# Sheet1.net
KiCad netlist of a schematic drawn in Altium Designer
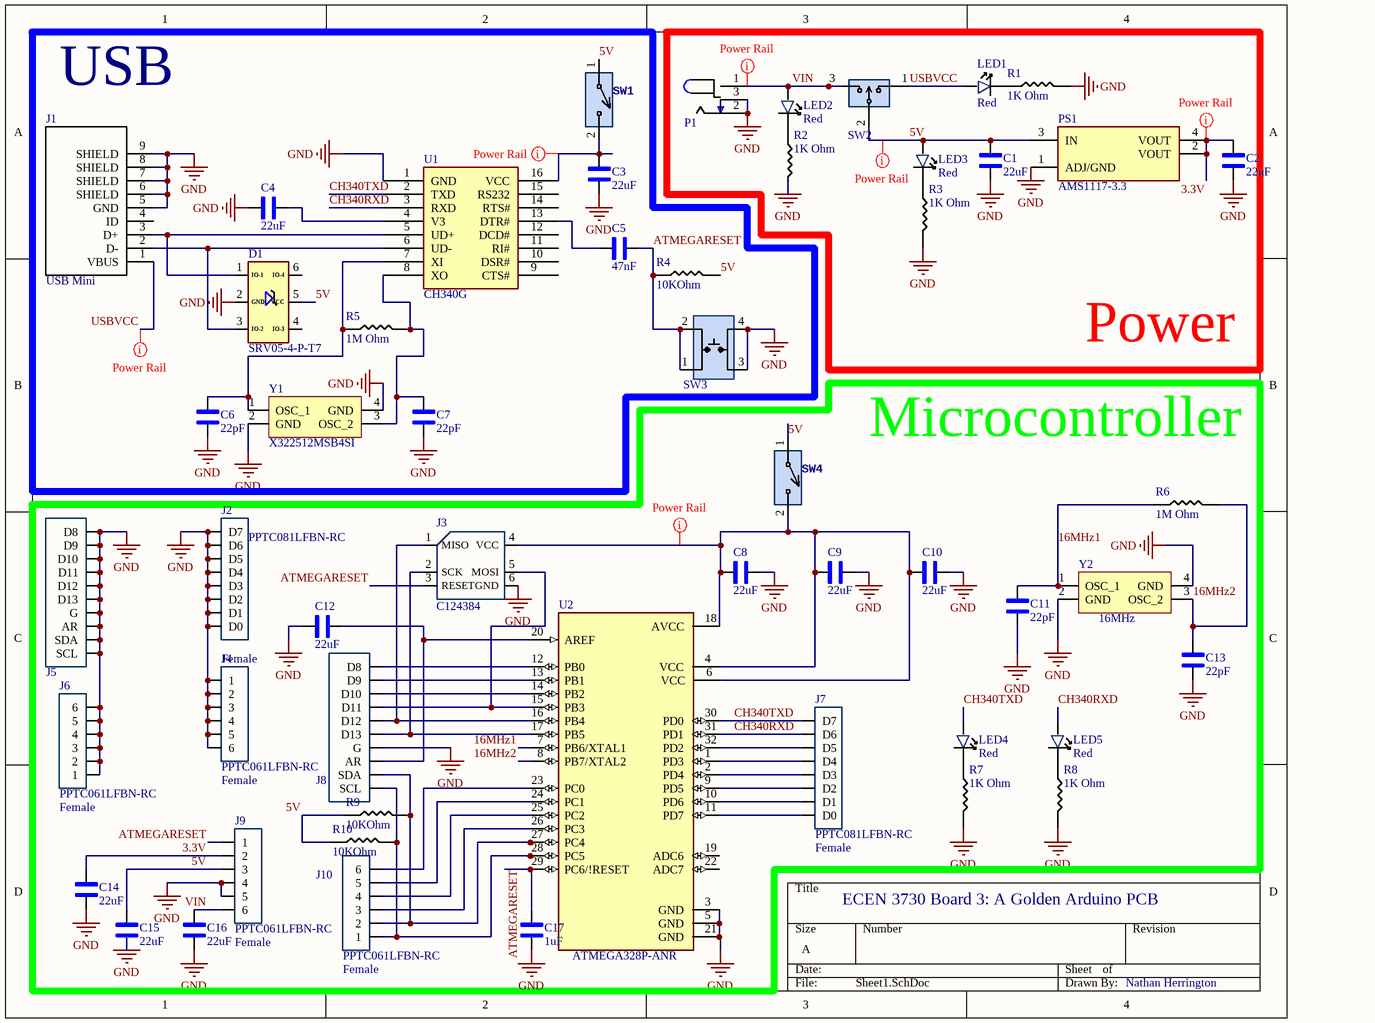
[diagram p0: Sheet1.SchDoc]

(export (version "E")
  (design (tool "Eeschema 10.0.6"))
  (components
    (comp (ref "C1")
      (value "22uF")
      (footprint "1206_Passive_Capacitor")
      (description "22uF ±10% 25V X5R 1206 Multilayer Ceramic Capacitors MLCC - SMD/SMT RoHS")
      (fields (field (name "MFR PART #") "CL31A226KAHNNNE") (field (name "LCSC PART#") "C12891"))
      (libsource (lib "ECEN5730Lib_2023_05_DS") (part "C_22uF_1206"))
    )
    (comp (ref "C2")
      (value "22uF")
      (footprint "1206_Passive_Capacitor")
      (description "22uF ±10% 25V X5R 1206 Multilayer Ceramic Capacitors MLCC - SMD/SMT RoHS")
      (fields (field (name "MFR PART #") "CL31A226KAHNNNE") (field (name "LCSC PART#") "C12891"))
      (libsource (lib "ECEN5730Lib_2023_05_DS") (part "C_22uF_1206"))
    )
    (comp (ref "C3")
      (value "22uF")
      (footprint "1206_Passive_Capacitor")
      (description "22uF ±10% 25V X5R 1206 Multilayer Ceramic Capacitors MLCC - SMD/SMT RoHS")
      (fields (field (name "MFR PART #") "CL31A226KAHNNNE") (field (name "LCSC PART#") "C12891"))
      (libsource (lib "ECEN5730Lib_2023_05_DS") (part "C_22uF_1206"))
    )
    (comp (ref "C4")
      (value "22uF")
      (footprint "1206_Passive_Capacitor")
      (description "22uF ±10% 25V X5R 1206 Multilayer Ceramic Capacitors MLCC - SMD/SMT RoHS")
      (fields (field (name "MFR PART #") "CL31A226KAHNNNE") (field (name "LCSC PART#") "C12891"))
      (libsource (lib "ECEN5730Lib_2023_05_DS") (part "C_22uF_1206"))
    )
    (comp (ref "C5")
      (value "47nF")
      (footprint "1206_Passive_Capacitor")
      (description "47nF ±5% 50V C0G 1206 Multilayer Ceramic Capacitors MLCC - SMD/SMT RoHS")
      (fields (field (name "LCSC PART#") "C21812") (field (name "MFR PART #") "GRM31M5C1H473JA01L"))
      (libsource (lib "ECEN5730Lib_2023_05_DS") (part "C_47nF_1206"))
    )
    (comp (ref "C6")
      (value "22pF")
      (footprint "1206_Passive_Capacitor")
      (description "22pF ±5% 1kV C0G 1206 Multilayer Ceramic Capacitors MLCC - SMD/SMT RoHS")
      (fields (field (name "MFR PART #") "CC1206JKNPOCBN220") (field (name "LCSC PART#") "C107174"))
      (libsource (lib "ECEN5730Lib_2023_05_DS") (part "C_22pF_1206"))
    )
    (comp (ref "C7")
      (value "22pF")
      (footprint "1206_Passive_Capacitor")
      (description "22pF ±5% 1kV C0G 1206 Multilayer Ceramic Capacitors MLCC - SMD/SMT RoHS")
      (fields (field (name "MFR PART #") "CC1206JKNPOCBN220") (field (name "LCSC PART#") "C107174"))
      (libsource (lib "ECEN5730Lib_2023_05_DS") (part "C_22pF_1206"))
    )
    (comp (ref "C8")
      (value "22uF")
      (footprint "1206_Passive_Capacitor")
      (description "22uF ±10% 25V X5R 1206 Multilayer Ceramic Capacitors MLCC - SMD/SMT RoHS")
      (fields (field (name "MFR PART #") "CL31A226KAHNNNE") (field (name "LCSC PART#") "C12891"))
      (libsource (lib "ECEN5730Lib_2023_05_DS") (part "C_22uF_1206"))
    )
    (comp (ref "C9")
      (value "22uF")
      (footprint "1206_Passive_Capacitor")
      (description "22uF ±10% 25V X5R 1206 Multilayer Ceramic Capacitors MLCC - SMD/SMT RoHS")
      (fields (field (name "MFR PART #") "CL31A226KAHNNNE") (field (name "LCSC PART#") "C12891"))
      (libsource (lib "ECEN5730Lib_2023_05_DS") (part "C_22uF_1206"))
    )
    (comp (ref "C10")
      (value "22uF")
      (footprint "1206_Passive_Capacitor")
      (description "22uF ±10% 25V X5R 1206 Multilayer Ceramic Capacitors MLCC - SMD/SMT RoHS")
      (fields (field (name "MFR PART #") "CL31A226KAHNNNE") (field (name "LCSC PART#") "C12891"))
      (libsource (lib "ECEN5730Lib_2023_05_DS") (part "C_22uF_1206"))
    )
    (comp (ref "C11")
      (value "22pF")
      (footprint "1206_Passive_Capacitor")
      (description "22pF ±5% 1kV C0G 1206 Multilayer Ceramic Capacitors MLCC - SMD/SMT RoHS")
      (fields (field (name "MFR PART #") "CC1206JKNPOCBN220") (field (name "LCSC PART#") "C107174"))
      (libsource (lib "ECEN5730Lib_2023_05_DS") (part "C_22pF_1206"))
    )
    (comp (ref "C12")
      (value "22uF")
      (footprint "1206_Passive_Capacitor")
      (description "22uF ±10% 25V X5R 1206 Multilayer Ceramic Capacitors MLCC - SMD/SMT RoHS")
      (fields (field (name "MFR PART #") "CL31A226KAHNNNE") (field (name "LCSC PART#") "C12891"))
      (libsource (lib "ECEN5730Lib_2023_05_DS") (part "C_22uF_1206"))
    )
    (comp (ref "C13")
      (value "22pF")
      (footprint "1206_Passive_Capacitor")
      (description "22pF ±5% 1kV C0G 1206 Multilayer Ceramic Capacitors MLCC - SMD/SMT RoHS")
      (fields (field (name "MFR PART #") "CC1206JKNPOCBN220") (field (name "LCSC PART#") "C107174"))
      (libsource (lib "ECEN5730Lib_2023_05_DS") (part "C_22pF_1206"))
    )
    (comp (ref "C14")
      (value "22uF")
      (footprint "1206_Passive_Capacitor")
      (description "22uF ±10% 25V X5R 1206 Multilayer Ceramic Capacitors MLCC - SMD/SMT RoHS")
      (fields (field (name "MFR PART #") "CL31A226KAHNNNE") (field (name "LCSC PART#") "C12891"))
      (libsource (lib "ECEN5730Lib_2023_05_DS") (part "C_22uF_1206"))
    )
    (comp (ref "C15")
      (value "22uF")
      (footprint "1206_Passive_Capacitor")
      (description "22uF ±10% 25V X5R 1206 Multilayer Ceramic Capacitors MLCC - SMD/SMT RoHS")
      (fields (field (name "MFR PART #") "CL31A226KAHNNNE") (field (name "LCSC PART#") "C12891"))
      (libsource (lib "ECEN5730Lib_2023_05_DS") (part "C_22uF_1206"))
    )
    (comp (ref "C16")
      (value "22uF")
      (footprint "1206_Passive_Capacitor")
      (description "22uF ±10% 25V X5R 1206 Multilayer Ceramic Capacitors MLCC - SMD/SMT RoHS")
      (fields (field (name "MFR PART #") "CL31A226KAHNNNE") (field (name "LCSC PART#") "C12891"))
      (libsource (lib "ECEN5730Lib_2023_05_DS") (part "C_22uF_1206"))
    )
    (comp (ref "C17")
      (value "1uF")
      (footprint "1206_Passive_Capacitor")
      (description "MULTILAYER CERAMIC CAPACITORS MLCC - SMD/SMT 1UF 50V 1206 ROHS")
      (fields (field (name "MFR PART #") "CL31B105KBHNNNE") (field (name "LCSC PART#") "C1848"))
      (libsource (lib "ECEN5730Lib_2023_05_DS") (part "C_1uF_1206"))
    )
    (comp (ref "D1")
      (value "SRV05-4-P-T7")
      (footprint "TVS")
      (description "TVS SOT-23-6 ROHS")
      (fields (field (name "LCSC PART#") "C85364"))
      (libsource (lib "ECEN5730Lib_2023_05_DS") (part "D_TVS_Diode"))
    )
    (comp (ref "J1")
      (value "USB Mini")
      (footprint "USB_MINI_B")
      (description "Through Hole USB Connectors RoHS")
      (fields (field (name "LCSC PART#") "C46398") (field (name "MFR PART #") "920-462A2021D10102"))
      (libsource (lib "ECEN5730Lib_2023_05_DS") (part "J_USB_B_Mini"))
    )
    (comp (ref "J2")
      (value "PPTC081LFBN-RC")
      (footprint "8_PIN_ARD-DIG_100MIL")
      (description "8 Position Header Connector 0.100\" (2.54mm) Through Hole Tin")
      (fields (field (name "LCSC PART#") "C27438") (field (name "ALTIUM_VALUE") "Female"))
      (libsource (lib "ECEN5730Lib_2023_05_DS") (part "JF_8_PIN_FEMA_ARD-Dig"))
    )
    (comp (ref "J3")
      (value "NRPN032PAEN-RC")
      (footprint "ICSP")
      (description "Connector Header Through Hole 6 position 0.079\" (2.00mm)")
      (fields (field (name "LCSC PART#") "C124384"))
      (libsource (lib "ECEN5730Lib_2023_05_DS") (part "J_ICSP"))
    )
    (comp (ref "J4")
      (value "PPTC061LFBN-RC")
      (footprint "6_PIN_100MIL -Female")
      (description "6 Position Header Connector 0.100\" (2.54mm) Through Hole Tin")
      (fields (field (name "LCSC PART#") "C40877") (field (name "ALTIUM_VALUE") "Female"))
      (libsource (lib "ECEN5730Lib_2023_05_DS") (part "JF_6_PIN_FEMALE"))
    )
    (comp (ref "J5")
      (value "PPTC101LFBN-RC")
      (footprint "10_PIN_ARDUINO_100MIL")
      (description "10 Position Header Connector 0.100\" (2.54mm) Through Hole Tin")
      (fields (field (name "LCSC PART#") "C225507"))
      (libsource (lib "ECEN5730Lib_2023_05_DS") (part "JF_10_PIN_FEMA_ARDUINO"))
    )
    (comp (ref "J6")
      (value "PPTC061LFBN-RC")
      (footprint "6_PIN_100MIL -Female")
      (description "6 Position Header Connector 0.100\" (2.54mm) Through Hole Tin")
      (fields (field (name "LCSC PART#") "C40877") (field (name "ALTIUM_VALUE") "Female"))
      (libsource (lib "") (part "JF_6_PIN_FEMALE_1"))
    )
    (comp (ref "J7")
      (value "PPTC081LFBN-RC")
      (footprint "8_PIN_ARD-DIG_100MIL")
      (description "8 Position Header Connector 0.100\" (2.54mm) Through Hole Tin")
      (fields (field (name "LCSC PART#") "C27438") (field (name "ALTIUM_VALUE") "Female"))
      (libsource (lib "ECEN5730Lib_2023_05_DS") (part "JF_8_PIN_FEMA_ARD-Dig"))
    )
    (comp (ref "J8")
      (value "PPTC101LFBN-RC")
      (footprint "10_PIN_ARDUINO_100MIL")
      (description "10 Position Header Connector 0.100\" (2.54mm) Through Hole Tin")
      (fields (field (name "LCSC PART#") "C225507"))
      (libsource (lib "ECEN5730Lib_2023_05_DS") (part "JF_10_PIN_FEMA_ARDUINO"))
    )
    (comp (ref "J9")
      (value "PPTC061LFBN-RC")
      (footprint "6_PIN_100MIL -Female")
      (description "6 Position Header Connector 0.100\" (2.54mm) Through Hole Tin")
      (fields (field (name "LCSC PART#") "C40877") (field (name "ALTIUM_VALUE") "Female"))
      (libsource (lib "ECEN5730Lib_2023_05_DS") (part "JF_6_PIN_FEMALE"))
    )
    (comp (ref "J10")
      (value "PPTC061LFBN-RC")
      (footprint "6_PIN_100MIL -Female")
      (description "6 Position Header Connector 0.100\" (2.54mm) Through Hole Tin")
      (fields (field (name "LCSC PART#") "C40877") (field (name "ALTIUM_VALUE") "Female"))
      (libsource (lib "") (part "JF_6_PIN_FEMALE_1"))
    )
    (comp (ref "LED1")
      (value "Red")
      (footprint "LED_1206")
      (description "Red 621~631nm 1206 Light Emitting Diodes (LED) RoHS")
      (fields (field (name "MFR PART #") "15-21/R6C-FQ1R1B/2T") (field (name "LCSC PART#") "C93133"))
      (libsource (lib "ECEN5730Lib_2023_05_DS") (part "LED_RED_1206"))
    )
    (comp (ref "LED2")
      (value "Red")
      (footprint "LED_1206")
      (description "Red 621~631nm 1206 Light Emitting Diodes (LED) RoHS")
      (fields (field (name "MFR PART #") "15-21/R6C-FQ1R1B/2T") (field (name "LCSC PART#") "C93133"))
      (libsource (lib "ECEN5730Lib_2023_05_DS") (part "LED_RED_1206"))
    )
    (comp (ref "LED3")
      (value "Red")
      (footprint "LED_1206")
      (description "Red 621~631nm 1206 Light Emitting Diodes (LED) RoHS")
      (fields (field (name "MFR PART #") "15-21/R6C-FQ1R1B/2T") (field (name "LCSC PART#") "C93133"))
      (libsource (lib "ECEN5730Lib_2023_05_DS") (part "LED_RED_1206"))
    )
    (comp (ref "LED4")
      (value "Red")
      (footprint "LED_1206")
      (description "Red 621~631nm 1206 Light Emitting Diodes (LED) RoHS")
      (fields (field (name "MFR PART #") "15-21/R6C-FQ1R1B/2T") (field (name "LCSC PART#") "C93133"))
      (libsource (lib "ECEN5730Lib_2023_05_DS") (part "LED_RED_1206"))
    )
    (comp (ref "LED5")
      (value "Red")
      (footprint "LED_1206")
      (description "Red 621~631nm 1206 Light Emitting Diodes (LED) RoHS")
      (fields (field (name "MFR PART #") "15-21/R6C-FQ1R1B/2T") (field (name "LCSC PART#") "C93133"))
      (libsource (lib "ECEN5730Lib_2023_05_DS") (part "LED_RED_1206"))
    )
    (comp (ref "P1")
      (value "Power Jack")
      (footprint "Power_Jack")
      (description "Power Barrel Connector Jack 2.10mm ID (0.083\"), 5.50mm OD (0.217\") Through Hole, Right Angle")
      (fields (field (name "MFR PART #") "PJ-102A") (field (name "LCSC PART#") "C136744"))
      (libsource (lib "ECEN5730Lib_2023_05_DS") (part "P_Power Jack"))
    )
    (comp (ref "PS1")
      (value "AMS1117-3.3")
      (footprint "LDO")
      (description "LOW DROPOUT REGULATORS(LDO) POSITIVE FIXED 1.3V @ 800MA 15V 3.3V 1A SOT-223 ROHS")
      (fields (field (name "LCSC PART#") "C6186"))
      (libsource (lib "ECEN5730Lib_2023_05_DS") (part "PS_AMS_LDO_3v3"))
    )
    (comp (ref "R1")
      (value "1K Ohm")
      (footprint "1206_Passive_Resitor")
      (description "CHIP RESISTOR - SURFACE MOUNT 1KOHMS ±1% 1/4W 1206 ROHS")
      (fields (field (name "MFR PART #") "RNCP1206FTD1K00CT") (field (name "LCSC PART#") "C4410"))
      (libsource (lib "ECEN5730Lib_2023_05_DS") (part "R_1K_1206"))
    )
    (comp (ref "R2")
      (value "1K Ohm")
      (footprint "1206_Passive_Resitor")
      (description "CHIP RESISTOR - SURFACE MOUNT 1KOHMS ±1% 1/4W 1206 ROHS")
      (fields (field (name "MFR PART #") "RNCP1206FTD1K00CT") (field (name "LCSC PART#") "C4410"))
      (libsource (lib "ECEN5730Lib_2023_05_DS") (part "R_1K_1206"))
    )
    (comp (ref "R3")
      (value "1K Ohm")
      (footprint "1206_Passive_Resitor")
      (description "CHIP RESISTOR - SURFACE MOUNT 1KOHMS ±1% 1/4W 1206 ROHS")
      (fields (field (name "MFR PART #") "RNCP1206FTD1K00CT") (field (name "LCSC PART#") "C4410"))
      (libsource (lib "ECEN5730Lib_2023_05_DS") (part "R_1K_1206"))
    )
    (comp (ref "R4")
      (value "10KOhm")
      (footprint "1206_Passive_Resitor")
      (description "10 kOhms ±5% 0.25W, 1/4W Chip Resistor 1206 (3216 Metric) Automotive AEC-Q200 Thick Film")
      (fields (field (name "MFR PART #") "RMCF1206FT10K0") (field (name "LCSC PART#") "C17902"))
      (libsource (lib "ECEN5730Lib_2023_05_DS") (part "R_10KOhm_1206"))
    )
    (comp (ref "R5")
      (value "1M Ohm")
      (footprint "1206_Passive_Resitor")
      (description "CHIP RESISTOR - SURFACE MOUNT 1MOHMS ±1% 1/4W 1206 ROHS")
      (fields (field (name "MFR PART #") "RMCF1206JT1M00") (field (name "LCSC PART#") "C17927"))
      (libsource (lib "ECEN5730Lib_2023_05_DS") (part "R_1M_1206"))
    )
    (comp (ref "R6")
      (value "1M Ohm")
      (footprint "1206_Passive_Resitor")
      (description "CHIP RESISTOR - SURFACE MOUNT 1MOHMS ±1% 1/4W 1206 ROHS")
      (fields (field (name "MFR PART #") "RMCF1206JT1M00") (field (name "LCSC PART#") "C17927"))
      (libsource (lib "ECEN5730Lib_2023_05_DS") (part "R_1M_1206"))
    )
    (comp (ref "R7")
      (value "1K Ohm")
      (footprint "1206_Passive_Resitor")
      (description "CHIP RESISTOR - SURFACE MOUNT 1KOHMS ±1% 1/4W 1206 ROHS")
      (fields (field (name "MFR PART #") "RNCP1206FTD1K00CT") (field (name "LCSC PART#") "C4410"))
      (libsource (lib "ECEN5730Lib_2023_05_DS") (part "R_1K_1206"))
    )
    (comp (ref "R8")
      (value "1K Ohm")
      (footprint "1206_Passive_Resitor")
      (description "CHIP RESISTOR - SURFACE MOUNT 1KOHMS ±1% 1/4W 1206 ROHS")
      (fields (field (name "MFR PART #") "RNCP1206FTD1K00CT") (field (name "LCSC PART#") "C4410"))
      (libsource (lib "ECEN5730Lib_2023_05_DS") (part "R_1K_1206"))
    )
    (comp (ref "R9")
      (value "10KOhm")
      (footprint "1206_Passive_Resitor")
      (description "10 kOhms ±5% 0.25W, 1/4W Chip Resistor 1206 (3216 Metric) Automotive AEC-Q200 Thick Film")
      (fields (field (name "MFR PART #") "RMCF1206FT10K0") (field (name "LCSC PART#") "C17902"))
      (libsource (lib "ECEN5730Lib_2023_05_DS") (part "R_10KOhm_1206"))
    )
    (comp (ref "R10")
      (value "10KOhm")
      (footprint "1206_Passive_Resitor")
      (description "10 kOhms ±5% 0.25W, 1/4W Chip Resistor 1206 (3216 Metric) Automotive AEC-Q200 Thick Film")
      (fields (field (name "MFR PART #") "RMCF1206FT10K0") (field (name "LCSC PART#") "C17902"))
      (libsource (lib "ECEN5730Lib_2023_05_DS") (part "R_10KOhm_1206"))
    )
    (comp (ref "SW1")
      (value "SW_2Pin_100mil_Switch")
      (footprint "2Pin-Header-Conn")
      (description "2Pin Header")
      (fields (field (name "LCSC PART#") "C124375"))
      (libsource (lib "ECEN5730Lib_2023_05_DS") (part "SW_2Pin_100mil_Switch"))
    )
    (comp (ref "SW2")
      (value "PREC003SAAN-RC")
      (footprint "3_PIN_100mil")
      (description "Connector Header Through Hole 3 position 0.100\" (2.54mm)")
      (fields (field (name "LCSC PART#") "C49257"))
      (libsource (lib "ECEN5730Lib_2023_05_DS") (part "SW_3Pin_100mil_Switch"))
    )
    (comp (ref "SW3")
      (value "TL3305AF160QG")
      (footprint "Switch_JLC")
      (description "Tactile Switch SPST-NO Top Actuated Surface Mount")
      (fields (field (name "MFR PART #") "KH-4.5X4.5X4.3H-STM") (field (name "LCSC PART#") "C2837550"))
      (libsource (lib "ECEN5730Lib_2023_05_DS") (part "SW_Push_Button_JLC"))
    )
    (comp (ref "SW4")
      (value "SW_2Pin_100mil_Switch")
      (footprint "2Pin-Header-Conn")
      (description "2Pin Header")
      (fields (field (name "LCSC PART#") "C124375"))
      (libsource (lib "ECEN5730Lib_2023_05_DS") (part "SW_2Pin_100mil_Switch"))
    )
    (comp (ref "U1")
      (value "CH340G")
      (footprint "USB to serial")
      (description "Transceiver USB 2.0 2Mbps SOP-16_150mil USB ICs RoHS")
      (fields (field (name "LCSC PART#") "C14267"))
      (libsource (lib "ECEN5730Lib_2023_05_DS") (part "U_USBtoSerial"))
    )
    (comp (ref "U2")
      (value "ATMEGA328P-ANR")
      (footprint "ATMega328P")
      (description "AVR AVR® ATmega Microcontroller IC 8-Bit 20MHz 32KB (16K x 16) FLASH 32-TQFP (7x7)")
      (fields (field (name "MFR PART #") "ATMEGA328P-AU") (field (name "LCSC PART#") "C14877"))
      (libsource (lib "ECEN5730Lib_2023_05_DS") (part "U_ATMega328P"))
    )
    (comp (ref "Y1")
      (value "X322512MSB4SI")
      (footprint "Crystal resonator")
      (description "SMD Crystal Resonators 12MHz ±10ppm SMD-3225_4P RoHS")
      (fields (field (name "LCSC PART#") "C9002"))
      (libsource (lib "ECEN5730Lib_2023_05_DS") (part "X_12MHz_Res"))
    )
    (comp (ref "Y2")
      (value "16MHz")
      (footprint "Crystal resonator")
      (description "±10ppm 16000000Hz -40℃~85℃ 贴片无源晶振 60Ω 9pF SMD3225-4P Crystals ROHS")
      (fields (field (name "LCSC PART#") "C13738") (field (name "MFR PART #") "X322516MLB4SI"))
      (libsource (lib "ECEN5730Lib_2023_05_DS") (part "X_16Mhz_Res"))
    )
  )
  (nets
    (net (code "1") (name "/3.3V") (class "Default")
      (node (ref "C14") (pin "1") (pinfunction "1_1") (pintype "passive"))
      (node (ref "C2") (pin "2") (pinfunction "2_2") (pintype "passive"))
      (node (ref "J9") (pin "2") (pinfunction "2_2") (pintype "passive"))
      (node (ref "PS1") (pin "2") (pinfunction "VOUT_2") (pintype "power_in"))
      (node (ref "PS1") (pin "4") (pinfunction "VOUT_4") (pintype "power_in"))
    )
    (net (code "2") (name "/5V") (class "Default")
      (node (ref "C1") (pin "2") (pinfunction "2_2") (pintype "passive"))
      (node (ref "C15") (pin "1") (pinfunction "1_1") (pintype "passive"))
      (node (ref "D1") (pin "5") (pinfunction "VCC_5") (pintype "passive"))
      (node (ref "J9") (pin "3") (pinfunction "3_3") (pintype "passive"))
      (node (ref "LED3") (pin "1") (pinfunction "1_1") (pintype "passive"))
      (node (ref "PS1") (pin "3") (pinfunction "IN_3") (pintype "power_in"))
      (node (ref "R10") (pin "1") (pinfunction "1_1") (pintype "passive"))
      (node (ref "R4") (pin "2") (pinfunction "2_2") (pintype "passive"))
      (node (ref "R9") (pin "1") (pinfunction "1_1") (pintype "passive"))
      (node (ref "SW1") (pin "1") (pinfunction "1_1") (pintype "passive"))
      (node (ref "SW2") (pin "2") (pinfunction "2_2") (pintype "passive"))
      (node (ref "SW4") (pin "1") (pinfunction "1_1") (pintype "passive"))
    )
    (net (code "3") (name "/16MHz1") (class "Default")
      (node (ref "C11") (pin "1") (pinfunction "1_1") (pintype "passive"))
      (node (ref "R6") (pin "1") (pinfunction "1_1") (pintype "passive"))
      (node (ref "U2") (pin "7") (pinfunction "PB6/XTAL1_7") (pintype "bidirectional"))
      (node (ref "Y2") (pin "1") (pinfunction "OSC_1_1") (pintype "passive"))
    )
    (net (code "4") (name "/16MHz2") (class "Default")
      (node (ref "C13") (pin "1") (pinfunction "1_1") (pintype "passive"))
      (node (ref "R6") (pin "2") (pinfunction "2_2") (pintype "passive"))
      (node (ref "U2") (pin "8") (pinfunction "PB7/XTAL2_8") (pintype "bidirectional"))
      (node (ref "Y2") (pin "3") (pinfunction "OSC_2_3") (pintype "passive"))
    )
    (net (code "5") (name "/ATMEGARESET") (class "Default")
      (node (ref "C17") (pin "1") (pinfunction "1_1") (pintype "passive"))
      (node (ref "C5") (pin "2") (pinfunction "2_2") (pintype "passive"))
      (node (ref "J3") (pin "3") (pinfunction "RESET_3") (pintype "passive"))
      (node (ref "J9") (pin "1") (pinfunction "1_1") (pintype "passive"))
      (node (ref "R4") (pin "1") (pinfunction "1_1") (pintype "passive"))
      (node (ref "SW3") (pin "1") (pinfunction "1_1") (pintype "passive"))
      (node (ref "SW3") (pin "2") (pinfunction "2_2") (pintype "passive"))
      (node (ref "U2") (pin "29") (pinfunction "PC6/!RESET_29") (pintype "bidirectional"))
    )
    (net (code "6") (name "/CH340RXD") (class "Default")
      (node (ref "J7") (pin "2") (pinfunction "D6_2") (pintype "passive"))
      (node (ref "LED5") (pin "1") (pinfunction "1_1") (pintype "passive"))
      (node (ref "U1") (pin "3") (pinfunction "RXD_3") (pintype "passive"))
      (node (ref "U2") (pin "31") (pinfunction "PD1_31") (pintype "bidirectional"))
    )
    (net (code "7") (name "/CH340TXD") (class "Default")
      (node (ref "J7") (pin "1") (pinfunction "D7_1") (pintype "passive"))
      (node (ref "LED4") (pin "1") (pinfunction "1_1") (pintype "passive"))
      (node (ref "U1") (pin "2") (pinfunction "TXD_2") (pintype "passive"))
      (node (ref "U2") (pin "30") (pinfunction "PD0_30") (pintype "bidirectional"))
    )
    (net (code "8") (name "/USBVCC") (class "Default")
      (node (ref "J1") (pin "1") (pinfunction "VBUS_1") (pintype "passive"))
      (node (ref "LED1") (pin "1") (pinfunction "1_1") (pintype "passive"))
      (node (ref "SW2") (pin "1") (pinfunction "1_1") (pintype "passive"))
    )
    (net (code "9") (name "/VIN") (class "Default")
      (node (ref "C16") (pin "2") (pinfunction "2_2") (pintype "passive"))
      (node (ref "J9") (pin "6") (pinfunction "6_6") (pintype "passive"))
      (node (ref "LED2") (pin "1") (pinfunction "1_1") (pintype "passive"))
      (node (ref "P1") (pin "1") (pinfunction "1_1") (pintype "power_in"))
      (node (ref "SW2") (pin "3") (pinfunction "3_3") (pintype "passive"))
    )
    (net (code "10") (name "GND") (class "Default")
      (node (ref "C1") (pin "1") (pinfunction "1_1") (pintype "passive"))
      (node (ref "C10") (pin "2") (pinfunction "2_2") (pintype "passive"))
      (node (ref "C11") (pin "2") (pinfunction "2_2") (pintype "passive"))
      (node (ref "C12") (pin "1") (pinfunction "1_1") (pintype "passive"))
      (node (ref "C13") (pin "2") (pinfunction "2_2") (pintype "passive"))
      (node (ref "C14") (pin "2") (pinfunction "2_2") (pintype "passive"))
      (node (ref "C15") (pin "2") (pinfunction "2_2") (pintype "passive"))
      (node (ref "C16") (pin "1") (pinfunction "1_1") (pintype "passive"))
      (node (ref "C17") (pin "2") (pinfunction "2_2") (pintype "passive"))
      (node (ref "C2") (pin "1") (pinfunction "1_1") (pintype "passive"))
      (node (ref "C3") (pin "2") (pinfunction "2_2") (pintype "passive"))
      (node (ref "C4") (pin "1") (pinfunction "1_1") (pintype "passive"))
      (node (ref "C6") (pin "1") (pinfunction "1_1") (pintype "passive"))
      (node (ref "C7") (pin "1") (pinfunction "1_1") (pintype "passive"))
      (node (ref "C8") (pin "2") (pinfunction "2_2") (pintype "passive"))
      (node (ref "C9") (pin "2") (pinfunction "2_2") (pintype "passive"))
      (node (ref "D1") (pin "2") (pinfunction "GND_2") (pintype "passive"))
      (node (ref "J1") (pin "5") (pinfunction "GND_5") (pintype "passive"))
      (node (ref "J1") (pin "6") (pinfunction "SHIELD_6") (pintype "passive"))
      (node (ref "J1") (pin "7") (pinfunction "SHIELD_7") (pintype "passive"))
      (node (ref "J1") (pin "8") (pinfunction "SHIELD_8") (pintype "passive"))
      (node (ref "J1") (pin "9") (pinfunction "SHIELD_9") (pintype "passive"))
      (node (ref "J2") (pin "1") (pinfunction "D7_1") (pintype "passive"))
      (node (ref "J2") (pin "2") (pinfunction "D6_2") (pintype "passive"))
      (node (ref "J2") (pin "3") (pinfunction "D5_3") (pintype "passive"))
      (node (ref "J2") (pin "4") (pinfunction "D4_4") (pintype "passive"))
      (node (ref "J2") (pin "5") (pinfunction "D3_5") (pintype "passive"))
      (node (ref "J2") (pin "6") (pinfunction "D2_6") (pintype "passive"))
      (node (ref "J2") (pin "7") (pinfunction "D1_7") (pintype "passive"))
      (node (ref "J2") (pin "8") (pinfunction "D0_8") (pintype "passive"))
      (node (ref "J3") (pin "6") (pinfunction "GND_6") (pintype "passive"))
      (node (ref "J4") (pin "1") (pinfunction "1_1") (pintype "passive"))
      (node (ref "J4") (pin "2") (pinfunction "2_2") (pintype "passive"))
      (node (ref "J4") (pin "3") (pinfunction "3_3") (pintype "passive"))
      (node (ref "J4") (pin "4") (pinfunction "4_4") (pintype "passive"))
      (node (ref "J4") (pin "5") (pinfunction "5_5") (pintype "passive"))
      (node (ref "J4") (pin "6") (pinfunction "6_6") (pintype "passive"))
      (node (ref "J5") (pin "1") (pinfunction "SCL_1") (pintype "passive"))
      (node (ref "J5") (pin "10") (pinfunction "D8_10") (pintype "passive"))
      (node (ref "J5") (pin "2") (pinfunction "SDA_2") (pintype "passive"))
      (node (ref "J5") (pin "3") (pinfunction "AR_3") (pintype "passive"))
      (node (ref "J5") (pin "4") (pinfunction "G_4") (pintype "passive"))
      (node (ref "J5") (pin "5") (pinfunction "D13_5") (pintype "passive"))
      (node (ref "J5") (pin "6") (pinfunction "D12_6") (pintype "passive"))
      (node (ref "J5") (pin "7") (pinfunction "D11_7") (pintype "passive"))
      (node (ref "J5") (pin "8") (pinfunction "D10_8") (pintype "passive"))
      (node (ref "J5") (pin "9") (pinfunction "D9_9") (pintype "passive"))
      (node (ref "J6") (pin "1") (pinfunction "1_1") (pintype "passive"))
      (node (ref "J6") (pin "2") (pinfunction "2_2") (pintype "passive"))
      (node (ref "J6") (pin "3") (pinfunction "3_3") (pintype "passive"))
      (node (ref "J6") (pin "4") (pinfunction "4_4") (pintype "passive"))
      (node (ref "J6") (pin "5") (pinfunction "5_5") (pintype "passive"))
      (node (ref "J6") (pin "6") (pinfunction "6_6") (pintype "passive"))
      (node (ref "J8") (pin "4") (pinfunction "G_4") (pintype "passive"))
      (node (ref "J9") (pin "4") (pinfunction "4_4") (pintype "passive"))
      (node (ref "J9") (pin "5") (pinfunction "5_5") (pintype "passive"))
      (node (ref "P1") (pin "2") (pinfunction "2_2") (pintype "power_in"))
      (node (ref "P1") (pin "3") (pinfunction "3_3") (pintype "power_in"))
      (node (ref "PS1") (pin "1") (pinfunction "ADJ/GND_1") (pintype "passive"))
      (node (ref "R1") (pin "2") (pinfunction "2_2") (pintype "passive"))
      (node (ref "R2") (pin "2") (pinfunction "2_2") (pintype "passive"))
      (node (ref "R3") (pin "2") (pinfunction "2_2") (pintype "passive"))
      (node (ref "R7") (pin "2") (pinfunction "2_2") (pintype "passive"))
      (node (ref "R8") (pin "2") (pinfunction "2_2") (pintype "passive"))
      (node (ref "SW3") (pin "3") (pinfunction "3_3") (pintype "passive"))
      (node (ref "SW3") (pin "4") (pinfunction "4_4") (pintype "passive"))
      (node (ref "U1") (pin "1") (pinfunction "GND_1") (pintype "passive"))
      (node (ref "U2") (pin "21") (pinfunction "GND_21") (pintype "power_in"))
      (node (ref "U2") (pin "3") (pinfunction "GND_3") (pintype "power_in"))
      (node (ref "U2") (pin "5") (pinfunction "GND_5") (pintype "power_in"))
      (node (ref "Y1") (pin "2") (pinfunction "GND_2") (pintype "passive"))
      (node (ref "Y1") (pin "4") (pinfunction "GND_4") (pintype "passive"))
      (node (ref "Y2") (pin "2") (pinfunction "GND_2") (pintype "passive"))
      (node (ref "Y2") (pin "4") (pinfunction "GND_4") (pintype "passive"))
    )
    (net (code "11") (name "Net-(D1-IO-1)") (class "Default")
      (node (ref "D1") (pin "1") (pinfunction "IO-1_1") (pintype "passive"))
      (node (ref "J1") (pin "3") (pinfunction "D+_3") (pintype "passive"))
      (node (ref "U1") (pin "5") (pinfunction "UD+_5") (pintype "passive"))
    )
    (net (code "12") (name "Net-(D1-IO-2)") (class "Default")
      (node (ref "D1") (pin "3") (pinfunction "IO-2_3") (pintype "passive"))
      (node (ref "J1") (pin "2") (pinfunction "D-_2") (pintype "passive"))
      (node (ref "U1") (pin "6") (pinfunction "UD-_6") (pintype "passive"))
    )
    (net (code "13") (name "Net-(J3-MISO)") (class "Default")
      (node (ref "J3") (pin "1") (pinfunction "MISO_1") (pintype "passive"))
      (node (ref "J8") (pin "6") (pinfunction "D12_6") (pintype "passive"))
      (node (ref "U2") (pin "16") (pinfunction "PB4_16") (pintype "bidirectional"))
    )
    (net (code "14") (name "Net-(J3-MOSI)") (class "Default")
      (node (ref "J3") (pin "5") (pinfunction "MOSI_5") (pintype "passive"))
      (node (ref "J8") (pin "7") (pinfunction "D11_7") (pintype "passive"))
      (node (ref "U2") (pin "15") (pinfunction "PB3_15") (pintype "bidirectional"))
    )
    (net (code "15") (name "Net-(J3-SCK)") (class "Default")
      (node (ref "J3") (pin "2") (pinfunction "SCK_2") (pintype "passive"))
      (node (ref "J8") (pin "5") (pinfunction "D13_5") (pintype "passive"))
      (node (ref "U2") (pin "17") (pinfunction "PB5_17") (pintype "bidirectional"))
    )
    (net (code "16") (name "Net-(J3-VCC)") (class "Default")
      (node (ref "C10") (pin "1") (pinfunction "1_1") (pintype "passive"))
      (node (ref "C8") (pin "1") (pinfunction "1_1") (pintype "passive"))
      (node (ref "C9") (pin "1") (pinfunction "1_1") (pintype "passive"))
      (node (ref "J3") (pin "4") (pinfunction "VCC_4") (pintype "passive"))
      (node (ref "SW4") (pin "2") (pinfunction "2_2") (pintype "passive"))
      (node (ref "U2") (pin "18") (pinfunction "AVCC_18") (pintype "power_in"))
      (node (ref "U2") (pin "4") (pinfunction "VCC_4") (pintype "power_in"))
      (node (ref "U2") (pin "6") (pinfunction "VCC_6") (pintype "power_in"))
    )
    (net (code "17") (name "Net-(J7-D0)") (class "Default")
      (node (ref "J7") (pin "8") (pinfunction "D0_8") (pintype "passive"))
      (node (ref "U2") (pin "11") (pinfunction "PD7_11") (pintype "bidirectional"))
    )
    (net (code "18") (name "Net-(J7-D1)") (class "Default")
      (node (ref "J7") (pin "7") (pinfunction "D1_7") (pintype "passive"))
      (node (ref "U2") (pin "10") (pinfunction "PD6_10") (pintype "bidirectional"))
    )
    (net (code "19") (name "Net-(J7-D2)") (class "Default")
      (node (ref "J7") (pin "6") (pinfunction "D2_6") (pintype "passive"))
      (node (ref "U2") (pin "9") (pinfunction "PD5_9") (pintype "bidirectional"))
    )
    (net (code "20") (name "Net-(J7-D3)") (class "Default")
      (node (ref "J7") (pin "5") (pinfunction "D3_5") (pintype "passive"))
      (node (ref "U2") (pin "2") (pinfunction "PD4_2") (pintype "bidirectional"))
    )
    (net (code "21") (name "Net-(J7-D4)") (class "Default")
      (node (ref "J7") (pin "4") (pinfunction "D4_4") (pintype "passive"))
      (node (ref "U2") (pin "1") (pinfunction "PD3_1") (pintype "bidirectional"))
    )
    (net (code "22") (name "Net-(J7-D5)") (class "Default")
      (node (ref "J7") (pin "3") (pinfunction "D5_3") (pintype "passive"))
      (node (ref "U2") (pin "32") (pinfunction "PD2_32") (pintype "bidirectional"))
    )
    (net (code "23") (name "Net-(J8-AR)") (class "Default")
      (node (ref "C12") (pin "2") (pinfunction "2_2") (pintype "passive"))
      (node (ref "J8") (pin "3") (pinfunction "AR_3") (pintype "passive"))
      (node (ref "U2") (pin "20") (pinfunction "AREF_20") (pintype "input"))
    )
    (net (code "24") (name "Net-(J8-D8)") (class "Default")
      (node (ref "J8") (pin "10") (pinfunction "D8_10") (pintype "passive"))
      (node (ref "U2") (pin "12") (pinfunction "PB0_12") (pintype "bidirectional"))
    )
    (net (code "25") (name "Net-(J8-D9)") (class "Default")
      (node (ref "J8") (pin "9") (pinfunction "D9_9") (pintype "passive"))
      (node (ref "U2") (pin "13") (pinfunction "PB1_13") (pintype "bidirectional"))
    )
    (net (code "26") (name "Net-(J8-D10)") (class "Default")
      (node (ref "J8") (pin "8") (pinfunction "D10_8") (pintype "passive"))
      (node (ref "U2") (pin "14") (pinfunction "PB2_14") (pintype "bidirectional"))
    )
    (net (code "27") (name "Net-(J8-SCL)") (class "Default")
      (node (ref "J10") (pin "1") (pinfunction "1_1") (pintype "passive"))
      (node (ref "J8") (pin "1") (pinfunction "SCL_1") (pintype "passive"))
      (node (ref "R10") (pin "2") (pinfunction "2_2") (pintype "passive"))
      (node (ref "U2") (pin "28") (pinfunction "PC5_28") (pintype "bidirectional"))
    )
    (net (code "28") (name "Net-(J8-SDA)") (class "Default")
      (node (ref "J10") (pin "2") (pinfunction "2_2") (pintype "passive"))
      (node (ref "J8") (pin "2") (pinfunction "SDA_2") (pintype "passive"))
      (node (ref "R9") (pin "2") (pinfunction "2_2") (pintype "passive"))
      (node (ref "U2") (pin "27") (pinfunction "PC4_27") (pintype "bidirectional"))
    )
    (net (code "29") (name "Net-(LED1-Pad2)") (class "Default")
      (node (ref "LED1") (pin "2") (pinfunction "2_2") (pintype "passive"))
      (node (ref "R1") (pin "1") (pinfunction "1_1") (pintype "passive"))
    )
    (net (code "30") (name "Net-(LED2-Pad2)") (class "Default")
      (node (ref "LED2") (pin "2") (pinfunction "2_2") (pintype "passive"))
      (node (ref "R2") (pin "1") (pinfunction "1_1") (pintype "passive"))
    )
    (net (code "31") (name "Net-(LED3-Pad2)") (class "Default")
      (node (ref "LED3") (pin "2") (pinfunction "2_2") (pintype "passive"))
      (node (ref "R3") (pin "1") (pinfunction "1_1") (pintype "passive"))
    )
    (net (code "32") (name "Net-(LED4-Pad2)") (class "Default")
      (node (ref "LED4") (pin "2") (pinfunction "2_2") (pintype "passive"))
      (node (ref "R7") (pin "1") (pinfunction "1_1") (pintype "passive"))
    )
    (net (code "33") (name "Net-(LED5-Pad2)") (class "Default")
      (node (ref "LED5") (pin "2") (pinfunction "2_2") (pintype "passive"))
      (node (ref "R8") (pin "1") (pinfunction "1_1") (pintype "passive"))
    )
    (net (code "34") (name "Net-(U1-DTR#)") (class "Default")
      (node (ref "C5") (pin "1") (pinfunction "1_1") (pintype "passive"))
      (node (ref "U1") (pin "13") (pinfunction "DTR#_13") (pintype "passive"))
    )
    (net (code "35") (name "Net-(U1-V3)") (class "Default")
      (node (ref "C4") (pin "2") (pinfunction "2_2") (pintype "passive"))
      (node (ref "U1") (pin "4") (pinfunction "V3_4") (pintype "passive"))
    )
    (net (code "36") (name "Net-(U1-VCC)") (class "Default")
      (node (ref "C3") (pin "1") (pinfunction "1_1") (pintype "passive"))
      (node (ref "SW1") (pin "2") (pinfunction "2_2") (pintype "passive"))
      (node (ref "U1") (pin "16") (pinfunction "VCC_16") (pintype "passive"))
    )
    (net (code "37") (name "Net-(U1-XI)") (class "Default")
      (node (ref "C6") (pin "2") (pinfunction "2_2") (pintype "passive"))
      (node (ref "R5") (pin "1") (pinfunction "1_1") (pintype "passive"))
      (node (ref "U1") (pin "7") (pinfunction "XI_7") (pintype "passive"))
      (node (ref "Y1") (pin "1") (pinfunction "OSC_1_1") (pintype "passive"))
    )
    (net (code "38") (name "Net-(U1-XO)") (class "Default")
      (node (ref "C7") (pin "2") (pinfunction "2_2") (pintype "passive"))
      (node (ref "R5") (pin "2") (pinfunction "2_2") (pintype "passive"))
      (node (ref "U1") (pin "8") (pinfunction "XO_8") (pintype "passive"))
      (node (ref "Y1") (pin "3") (pinfunction "OSC_2_3") (pintype "passive"))
    )
    (net (code "39") (name "Net-(U2-PC0)") (class "Default")
      (node (ref "J10") (pin "6") (pinfunction "6_6") (pintype "passive"))
      (node (ref "U2") (pin "23") (pinfunction "PC0_23") (pintype "bidirectional"))
    )
    (net (code "40") (name "Net-(U2-PC1)") (class "Default")
      (node (ref "J10") (pin "5") (pinfunction "5_5") (pintype "passive"))
      (node (ref "U2") (pin "24") (pinfunction "PC1_24") (pintype "bidirectional"))
    )
    (net (code "41") (name "Net-(U2-PC2)") (class "Default")
      (node (ref "J10") (pin "4") (pinfunction "4_4") (pintype "passive"))
      (node (ref "U2") (pin "25") (pinfunction "PC2_25") (pintype "bidirectional"))
    )
    (net (code "42") (name "Net-(U2-PC3)") (class "Default")
      (node (ref "J10") (pin "3") (pinfunction "3_3") (pintype "passive"))
      (node (ref "U2") (pin "26") (pinfunction "PC3_26") (pintype "bidirectional"))
    )
    (net (code "43") (name "unconnected-(D1-IO-3-Pad4)") (class "Default")
      (node (ref "D1") (pin "4") (pinfunction "IO-3_4") (pintype "passive"))
    )
    (net (code "44") (name "unconnected-(D1-IO-4-Pad6)") (class "Default")
      (node (ref "D1") (pin "6") (pinfunction "IO-4_6") (pintype "passive"))
    )
    (net (code "45") (name "unconnected-(J1-ID-Pad4)") (class "Default")
      (node (ref "J1") (pin "4") (pinfunction "ID_4") (pintype "passive"))
    )
    (net (code "46") (name "unconnected-(U1-CTS#-Pad9)") (class "Default")
      (node (ref "U1") (pin "9") (pinfunction "CTS#_9") (pintype "passive"))
    )
    (net (code "47") (name "unconnected-(U1-DCD#-Pad12)") (class "Default")
      (node (ref "U1") (pin "12") (pinfunction "DCD#_12") (pintype "passive"))
    )
    (net (code "48") (name "unconnected-(U1-DSR#-Pad10)") (class "Default")
      (node (ref "U1") (pin "10") (pinfunction "DSR#_10") (pintype "passive"))
    )
    (net (code "49") (name "unconnected-(U1-RI#-Pad11)") (class "Default")
      (node (ref "U1") (pin "11") (pinfunction "RI#_11") (pintype "passive"))
    )
    (net (code "50") (name "unconnected-(U1-RS232-Pad15)") (class "Default")
      (node (ref "U1") (pin "15") (pinfunction "RS232_15") (pintype "passive"))
    )
    (net (code "51") (name "unconnected-(U1-RTS#-Pad14)") (class "Default")
      (node (ref "U1") (pin "14") (pinfunction "RTS#_14") (pintype "passive"))
    )
    (net (code "52") (name "unconnected-(U2-ADC6-Pad19)") (class "Default")
      (node (ref "U2") (pin "19") (pinfunction "ADC6_19") (pintype "bidirectional"))
    )
    (net (code "53") (name "unconnected-(U2-ADC7-Pad22)") (class "Default")
      (node (ref "U2") (pin "22") (pinfunction "ADC7_22") (pintype "bidirectional"))
    )
  )
)
